# FilterBoard_Schematic.net
KiCad netlist of a schematic drawn in Altium Designer
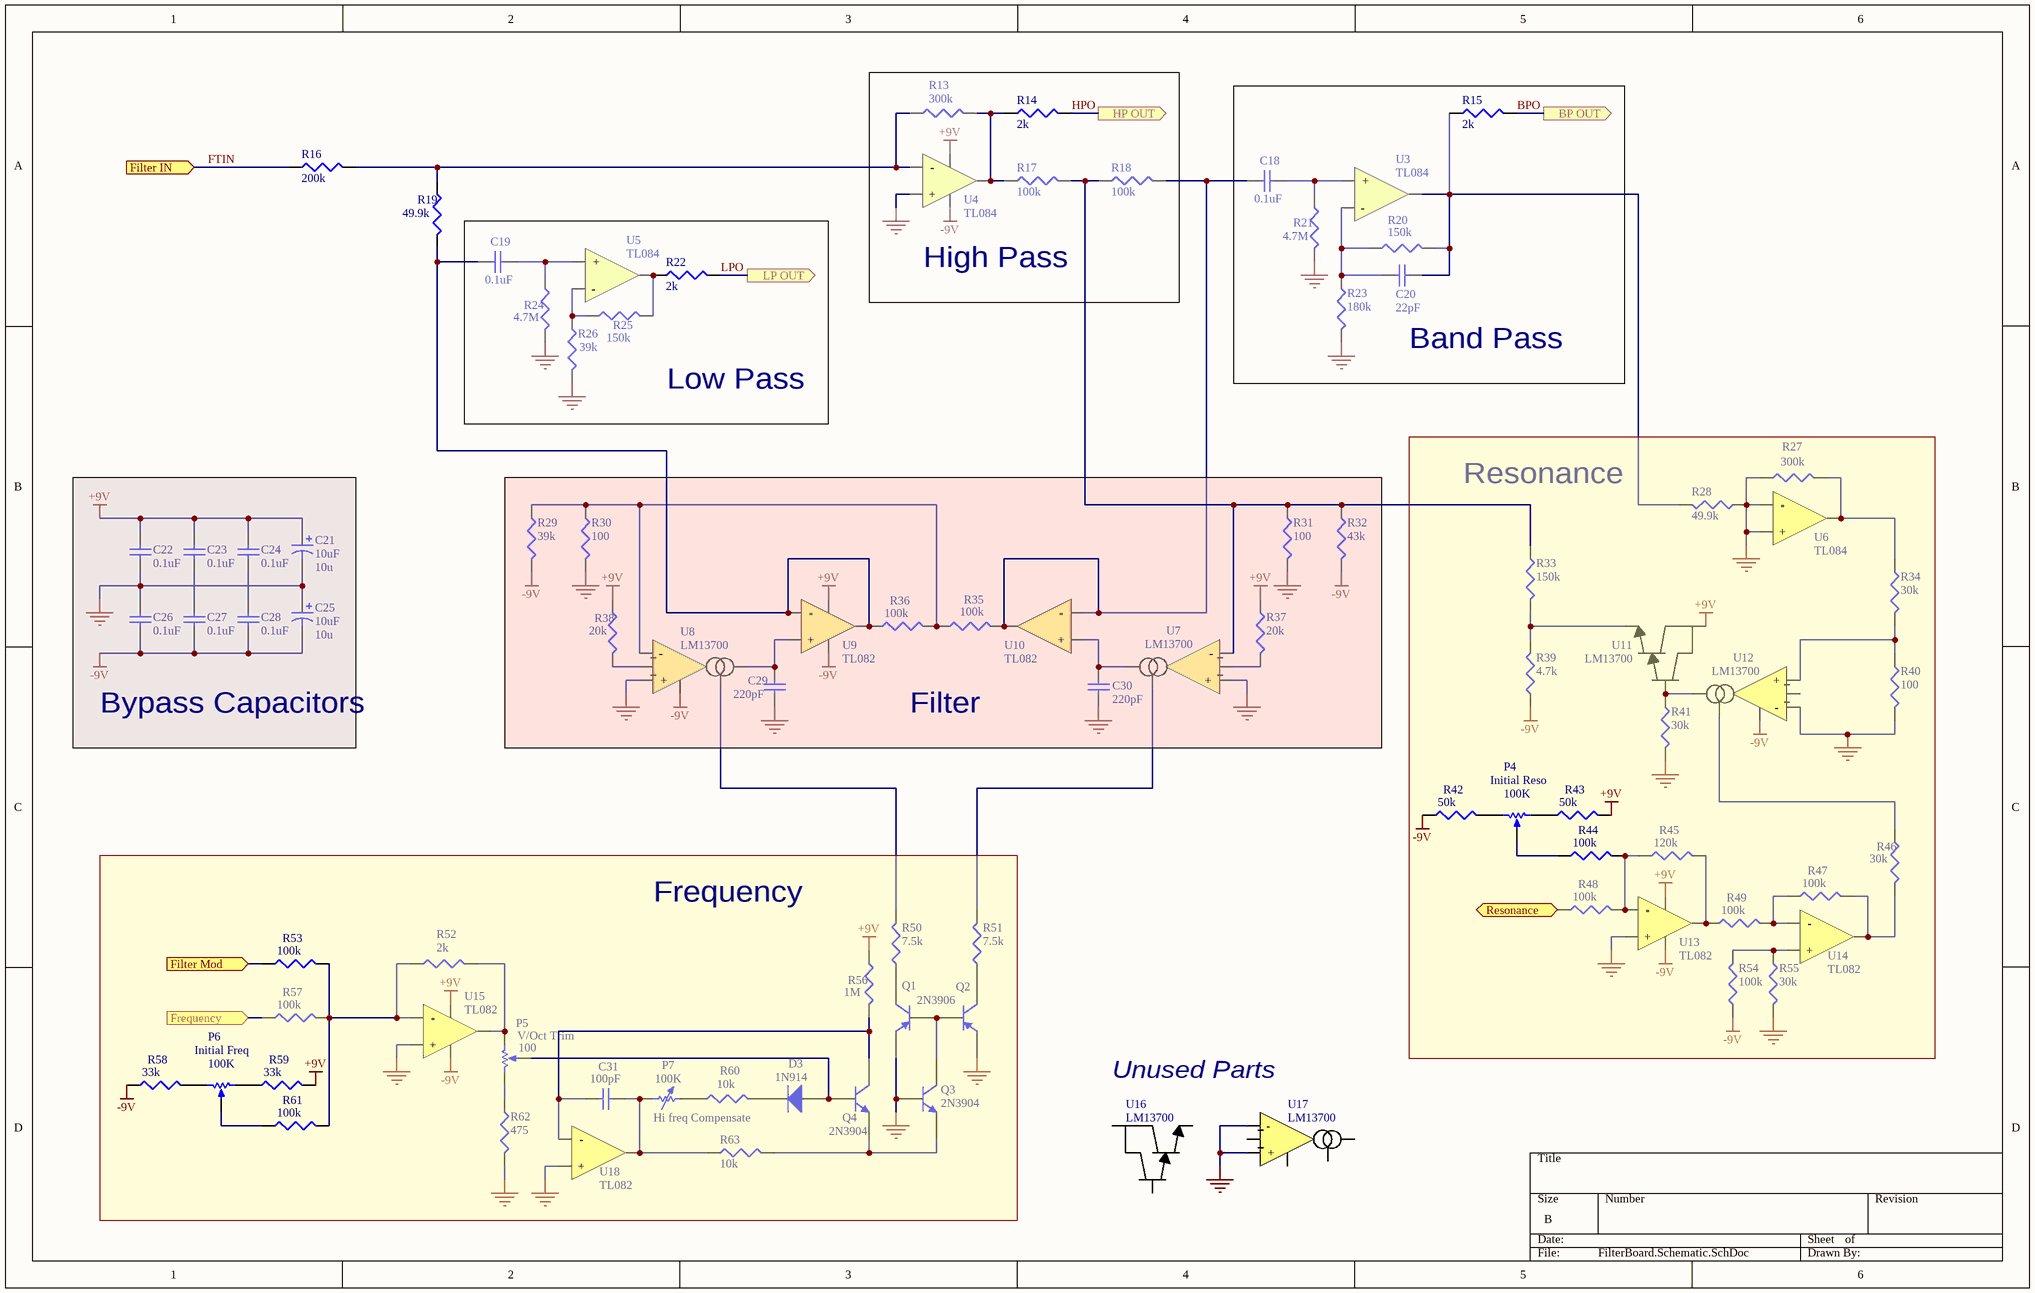
[diagram p0: FilterBoard.Schematic.SchDoc]

(export (version "E")
  (design (tool "Eeschema 10.0.6"))
  (components
    (comp (ref "C18")
      (value "0.1uF")
      (footprint "C1206")
      (description "Capacitor (Semiconductor SIM Model)")
      (fields (field (name "PUBLISHER") "Altium Limited"))
      (libsource (lib "Miscellaneous Devices") (part "Cap Semi"))
    )
    (comp (ref "C19")
      (value "0.1uF")
      (footprint "C1206")
      (description "Capacitor (Semiconductor SIM Model)")
      (fields (field (name "PUBLISHER") "Altium Limited"))
      (libsource (lib "Miscellaneous Devices") (part "Cap Semi"))
    )
    (comp (ref "C20")
      (value "22pF")
      (footprint "C1206")
      (description "Capacitor (Semiconductor SIM Model)")
      (fields (field (name "PUBLISHER") "Altium Limited"))
      (libsource (lib "Miscellaneous Devices") (part "Cap Semi"))
    )
    (comp (ref "C21")
      (value "10uF")
      (footprint "RB7.6-15")
      (description "Polarized Capacitor (Radial)")
      (fields (field (name "ALTIUM_VALUE") "10u") (field (name "PUBLISHER") "Altium Limited"))
      (libsource (lib "Miscellaneous Devices") (part "Cap Pol1"))
    )
    (comp (ref "C22")
      (value "0.1uF")
      (footprint "C1206")
      (description "Capacitor (Semiconductor SIM Model)")
      (fields (field (name "PUBLISHER") "Altium Limited"))
      (libsource (lib "Miscellaneous Devices") (part "Cap Semi"))
    )
    (comp (ref "C23")
      (value "0.1uF")
      (footprint "C1206")
      (description "Capacitor (Semiconductor SIM Model)")
      (fields (field (name "PUBLISHER") "Altium Limited"))
      (libsource (lib "Miscellaneous Devices") (part "Cap Semi"))
    )
    (comp (ref "C24")
      (value "0.1uF")
      (footprint "C1206")
      (description "Capacitor (Semiconductor SIM Model)")
      (fields (field (name "PUBLISHER") "Altium Limited"))
      (libsource (lib "Miscellaneous Devices") (part "Cap Semi"))
    )
    (comp (ref "C25")
      (value "10uF")
      (footprint "RB7.6-15")
      (description "Polarized Capacitor (Radial)")
      (fields (field (name "ALTIUM_VALUE") "10u") (field (name "PUBLISHER") "Altium Limited"))
      (libsource (lib "Miscellaneous Devices") (part "Cap Pol1"))
    )
    (comp (ref "C26")
      (value "0.1uF")
      (footprint "C1206")
      (description "Capacitor (Semiconductor SIM Model)")
      (fields (field (name "PUBLISHER") "Altium Limited"))
      (libsource (lib "Miscellaneous Devices") (part "Cap Semi"))
    )
    (comp (ref "C27")
      (value "0.1uF")
      (footprint "C1206")
      (description "Capacitor (Semiconductor SIM Model)")
      (fields (field (name "PUBLISHER") "Altium Limited"))
      (libsource (lib "Miscellaneous Devices") (part "Cap Semi"))
    )
    (comp (ref "C28")
      (value "0.1uF")
      (footprint "C1206")
      (description "Capacitor (Semiconductor SIM Model)")
      (fields (field (name "PUBLISHER") "Altium Limited"))
      (libsource (lib "Miscellaneous Devices") (part "Cap Semi"))
    )
    (comp (ref "C29")
      (value "220pF")
      (footprint "C1206")
      (description "Capacitor (Semiconductor SIM Model)")
      (fields (field (name "PUBLISHER") "Altium Limited"))
      (libsource (lib "Miscellaneous Devices") (part "Cap Semi"))
    )
    (comp (ref "C30")
      (value "220pF")
      (footprint "C1206")
      (description "Capacitor (Semiconductor SIM Model)")
      (fields (field (name "PUBLISHER") "Altium Limited"))
      (libsource (lib "Miscellaneous Devices") (part "Cap Semi"))
    )
    (comp (ref "C31")
      (value "100pF")
      (footprint "C1206")
      (description "Capacitor (Semiconductor SIM Model)")
      (fields (field (name "PUBLISHER") "Altium Limited"))
      (libsource (lib "Miscellaneous Devices") (part "Cap Semi"))
    )
    (comp (ref "D3")
      (value "1N914")
      (footprint "DO-41")
      (description "1 Amp General Purpose Rectifier")
      (fields (field (name "PUBLISHER") "Altium Limited"))
      (libsource (lib "Miscellaneous Devices") (part "Diode 1N4001"))
    )
    (comp (ref "P4")
      (value "Initial Reso")
      (footprint "VR5")
      (description "Potentiometer")
      (fields (field (name "ALTIUM_VALUE") "100K") (field (name "PUBLISHER") "Altium Limited"))
      (libsource (lib "Miscellaneous Devices") (part "RPot"))
    )
    (comp (ref "P5")
      (value "V/Oct Trim")
      (footprint "VR5")
      (description "Potentiometer")
      (fields (field (name "ALTIUM_VALUE") "100") (field (name "PUBLISHER") "Altium Limited"))
      (libsource (lib "Miscellaneous Devices") (part "RPot"))
    )
    (comp (ref "P6")
      (value "Initial Freq")
      (footprint "VR5")
      (description "Potentiometer")
      (fields (field (name "ALTIUM_VALUE") "100K") (field (name "PUBLISHER") "Altium Limited"))
      (libsource (lib "Miscellaneous Devices") (part "RPot"))
    )
    (comp (ref "P7")
      (value "Hi freq Compensate")
      (footprint "AXIAL-0.7")
      (description "Variable Resistor")
      (fields (field (name "ALTIUM_VALUE") "100K") (field (name "PUBLISHER") "Altium Limited"))
      (libsource (lib "Miscellaneous Devices") (part "Res Adj1"))
    )
    (comp (ref "Q1")
      (value "2N3906")
      (footprint "TO-92A")
      (description "PNP General Purpose Amplifier")
      (fields (field (name "PUBLISHER") "Altium Limited"))
      (libsource (lib "Miscellaneous Devices") (part "2N3906"))
    )
    (comp (ref "Q2")
      (value "2N3906")
      (footprint "TO-92A")
      (description "PNP General Purpose Amplifier")
      (fields (field (name "PUBLISHER") "Altium Limited"))
      (libsource (lib "Miscellaneous Devices") (part "2N3906"))
    )
    (comp (ref "Q3")
      (value "2N3904")
      (footprint "TO-92A")
      (description "NPN General Purpose Amplifier")
      (fields (field (name "PUBLISHER") "Altium Limited"))
      (libsource (lib "Miscellaneous Devices") (part "2N3904"))
    )
    (comp (ref "Q4")
      (value "2N3904")
      (footprint "TO-92A")
      (description "NPN General Purpose Amplifier")
      (fields (field (name "PUBLISHER") "Altium Limited"))
      (libsource (lib "Miscellaneous Devices") (part "2N3904"))
    )
    (comp (ref "R13")
      (value "300k")
      (footprint "J1-0603")
      (description "Resistor")
      (fields (field (name "PUBLISHER") "Altium Limited"))
      (libsource (lib "Miscellaneous Devices") (part "Res3"))
    )
    (comp (ref "R14")
      (value "2k")
      (footprint "J1-0603")
      (description "Resistor")
      (fields (field (name "PUBLISHER") "Altium Limited"))
      (libsource (lib "Miscellaneous Devices") (part "Res3"))
    )
    (comp (ref "R15")
      (value "2k")
      (footprint "J1-0603")
      (description "Resistor")
      (fields (field (name "PUBLISHER") "Altium Limited"))
      (libsource (lib "Miscellaneous Devices") (part "Res3"))
    )
    (comp (ref "R16")
      (value "200k")
      (footprint "J1-0603")
      (description "Resistor")
      (fields (field (name "PUBLISHER") "Altium Limited"))
      (libsource (lib "Miscellaneous Devices") (part "Res3"))
    )
    (comp (ref "R17")
      (value "100k")
      (footprint "J1-0603")
      (description "Resistor")
      (fields (field (name "PUBLISHER") "Altium Limited"))
      (libsource (lib "Miscellaneous Devices") (part "Res3"))
    )
    (comp (ref "R18")
      (value "100k")
      (footprint "J1-0603")
      (description "Resistor")
      (fields (field (name "PUBLISHER") "Altium Limited"))
      (libsource (lib "Miscellaneous Devices") (part "Res3"))
    )
    (comp (ref "R19")
      (value "49.9k")
      (footprint "J1-0603")
      (description "Resistor")
      (fields (field (name "PUBLISHER") "Altium Limited"))
      (libsource (lib "Miscellaneous Devices") (part "Res3"))
    )
    (comp (ref "R20")
      (value "150k")
      (footprint "J1-0603")
      (description "Resistor")
      (fields (field (name "PUBLISHER") "Altium Limited"))
      (libsource (lib "Miscellaneous Devices") (part "Res3"))
    )
    (comp (ref "R21")
      (value "4.7M")
      (footprint "J1-0603")
      (description "Resistor")
      (fields (field (name "PUBLISHER") "Altium Limited"))
      (libsource (lib "Miscellaneous Devices") (part "Res3"))
    )
    (comp (ref "R22")
      (value "2k")
      (footprint "J1-0603")
      (description "Resistor")
      (fields (field (name "PUBLISHER") "Altium Limited"))
      (libsource (lib "Miscellaneous Devices") (part "Res3"))
    )
    (comp (ref "R23")
      (value "180k")
      (footprint "J1-0603")
      (description "Resistor")
      (fields (field (name "PUBLISHER") "Altium Limited"))
      (libsource (lib "Miscellaneous Devices") (part "Res3"))
    )
    (comp (ref "R24")
      (value "4.7M")
      (footprint "J1-0603")
      (description "Resistor")
      (fields (field (name "PUBLISHER") "Altium Limited"))
      (libsource (lib "Miscellaneous Devices") (part "Res3"))
    )
    (comp (ref "R25")
      (value "150k")
      (footprint "J1-0603")
      (description "Resistor")
      (fields (field (name "PUBLISHER") "Altium Limited"))
      (libsource (lib "Miscellaneous Devices") (part "Res3"))
    )
    (comp (ref "R26")
      (value "39k")
      (footprint "J1-0603")
      (description "Resistor")
      (fields (field (name "PUBLISHER") "Altium Limited"))
      (libsource (lib "Miscellaneous Devices") (part "Res3"))
    )
    (comp (ref "R27")
      (value "300k")
      (footprint "J1-0603")
      (description "Resistor")
      (fields (field (name "PUBLISHER") "Altium Limited"))
      (libsource (lib "Miscellaneous Devices") (part "Res3"))
    )
    (comp (ref "R28")
      (value "49.9k")
      (footprint "J1-0603")
      (description "Resistor")
      (fields (field (name "PUBLISHER") "Altium Limited"))
      (libsource (lib "Miscellaneous Devices") (part "Res3"))
    )
    (comp (ref "R29")
      (value "39k")
      (footprint "J1-0603")
      (description "Resistor")
      (fields (field (name "PUBLISHER") "Altium Limited"))
      (libsource (lib "Miscellaneous Devices") (part "Res3"))
    )
    (comp (ref "R30")
      (value "100")
      (footprint "J1-0603")
      (description "Resistor")
      (fields (field (name "PUBLISHER") "Altium Limited"))
      (libsource (lib "Miscellaneous Devices") (part "Res3"))
    )
    (comp (ref "R31")
      (value "100")
      (footprint "J1-0603")
      (description "Resistor")
      (fields (field (name "PUBLISHER") "Altium Limited"))
      (libsource (lib "Miscellaneous Devices") (part "Res3"))
    )
    (comp (ref "R32")
      (value "43k")
      (footprint "J1-0603")
      (description "Resistor")
      (fields (field (name "PUBLISHER") "Altium Limited"))
      (libsource (lib "Miscellaneous Devices") (part "Res3"))
    )
    (comp (ref "R33")
      (value "150k")
      (footprint "J1-0603")
      (description "Resistor")
      (fields (field (name "PUBLISHER") "Altium Limited"))
      (libsource (lib "Miscellaneous Devices") (part "Res3"))
    )
    (comp (ref "R34")
      (value "30k")
      (footprint "J1-0603")
      (description "Resistor")
      (fields (field (name "PUBLISHER") "Altium Limited"))
      (libsource (lib "Miscellaneous Devices") (part "Res3"))
    )
    (comp (ref "R35")
      (value "100k")
      (footprint "J1-0603")
      (description "Resistor")
      (fields (field (name "PUBLISHER") "Altium Limited"))
      (libsource (lib "Miscellaneous Devices") (part "Res3"))
    )
    (comp (ref "R36")
      (value "100k")
      (footprint "J1-0603")
      (description "Resistor")
      (fields (field (name "PUBLISHER") "Altium Limited"))
      (libsource (lib "Miscellaneous Devices") (part "Res3"))
    )
    (comp (ref "R37")
      (value "20k")
      (footprint "J1-0603")
      (description "Resistor")
      (fields (field (name "PUBLISHER") "Altium Limited"))
      (libsource (lib "Miscellaneous Devices") (part "Res3"))
    )
    (comp (ref "R38")
      (value "20k")
      (footprint "J1-0603")
      (description "Resistor")
      (fields (field (name "PUBLISHER") "Altium Limited"))
      (libsource (lib "Miscellaneous Devices") (part "Res3"))
    )
    (comp (ref "R39")
      (value "4.7k")
      (footprint "J1-0603")
      (description "Resistor")
      (fields (field (name "PUBLISHER") "Altium Limited"))
      (libsource (lib "Miscellaneous Devices") (part "Res3"))
    )
    (comp (ref "R40")
      (value "100")
      (footprint "J1-0603")
      (description "Resistor")
      (fields (field (name "PUBLISHER") "Altium Limited"))
      (libsource (lib "Miscellaneous Devices") (part "Res3"))
    )
    (comp (ref "R41")
      (value "30k")
      (footprint "J1-0603")
      (description "Resistor")
      (fields (field (name "PUBLISHER") "Altium Limited"))
      (libsource (lib "Miscellaneous Devices") (part "Res3"))
    )
    (comp (ref "R42")
      (value "50k")
      (footprint "J1-0603")
      (description "Resistor")
      (fields (field (name "PUBLISHER") "Altium Limited"))
      (libsource (lib "Miscellaneous Devices") (part "Res3"))
    )
    (comp (ref "R43")
      (value "50k")
      (footprint "J1-0603")
      (description "Resistor")
      (fields (field (name "PUBLISHER") "Altium Limited"))
      (libsource (lib "Miscellaneous Devices") (part "Res3"))
    )
    (comp (ref "R44")
      (value "100k")
      (footprint "J1-0603")
      (description "Resistor")
      (fields (field (name "PUBLISHER") "Altium Limited"))
      (libsource (lib "Miscellaneous Devices") (part "Res3"))
    )
    (comp (ref "R45")
      (value "120k")
      (footprint "J1-0603")
      (description "Resistor")
      (fields (field (name "PUBLISHER") "Altium Limited"))
      (libsource (lib "Miscellaneous Devices") (part "Res3"))
    )
    (comp (ref "R46")
      (value "30k")
      (footprint "J1-0603")
      (description "Resistor")
      (fields (field (name "PUBLISHER") "Altium Limited"))
      (libsource (lib "Miscellaneous Devices") (part "Res3"))
    )
    (comp (ref "R47")
      (value "100k")
      (footprint "J1-0603")
      (description "Resistor")
      (fields (field (name "PUBLISHER") "Altium Limited"))
      (libsource (lib "Miscellaneous Devices") (part "Res3"))
    )
    (comp (ref "R48")
      (value "100k")
      (footprint "J1-0603")
      (description "Resistor")
      (fields (field (name "PUBLISHER") "Altium Limited"))
      (libsource (lib "Miscellaneous Devices") (part "Res3"))
    )
    (comp (ref "R49")
      (value "100k")
      (footprint "J1-0603")
      (description "Resistor")
      (fields (field (name "PUBLISHER") "Altium Limited"))
      (libsource (lib "Miscellaneous Devices") (part "Res3"))
    )
    (comp (ref "R50")
      (value "7.5k")
      (footprint "J1-0603")
      (description "Resistor")
      (fields (field (name "PUBLISHER") "Altium Limited"))
      (libsource (lib "Miscellaneous Devices") (part "Res3"))
    )
    (comp (ref "R51")
      (value "7.5k")
      (footprint "J1-0603")
      (description "Resistor")
      (fields (field (name "PUBLISHER") "Altium Limited"))
      (libsource (lib "Miscellaneous Devices") (part "Res3"))
    )
    (comp (ref "R52")
      (value "2k")
      (footprint "J1-0603")
      (description "Resistor")
      (fields (field (name "PUBLISHER") "Altium Limited"))
      (libsource (lib "Miscellaneous Devices") (part "Res3"))
    )
    (comp (ref "R53")
      (value "100k")
      (footprint "J1-0603")
      (description "Resistor")
      (fields (field (name "PUBLISHER") "Altium Limited"))
      (libsource (lib "Miscellaneous Devices") (part "Res3"))
    )
    (comp (ref "R54")
      (value "100k")
      (footprint "J1-0603")
      (description "Resistor")
      (fields (field (name "PUBLISHER") "Altium Limited"))
      (libsource (lib "Miscellaneous Devices") (part "Res3"))
    )
    (comp (ref "R55")
      (value "30k")
      (footprint "J1-0603")
      (description "Resistor")
      (fields (field (name "PUBLISHER") "Altium Limited"))
      (libsource (lib "Miscellaneous Devices") (part "Res3"))
    )
    (comp (ref "R56")
      (value "1M")
      (footprint "J1-0603")
      (description "Resistor")
      (fields (field (name "PUBLISHER") "Altium Limited"))
      (libsource (lib "Miscellaneous Devices") (part "Res3"))
    )
    (comp (ref "R57")
      (value "100k")
      (footprint "J1-0603")
      (description "Resistor")
      (fields (field (name "PUBLISHER") "Altium Limited"))
      (libsource (lib "Miscellaneous Devices") (part "Res3"))
    )
    (comp (ref "R58")
      (value "33k")
      (footprint "J1-0603")
      (description "Resistor")
      (fields (field (name "PUBLISHER") "Altium Limited"))
      (libsource (lib "Miscellaneous Devices") (part "Res3"))
    )
    (comp (ref "R59")
      (value "33k")
      (footprint "J1-0603")
      (description "Resistor")
      (fields (field (name "PUBLISHER") "Altium Limited"))
      (libsource (lib "Miscellaneous Devices") (part "Res3"))
    )
    (comp (ref "R60")
      (value "10k")
      (footprint "J1-0603")
      (description "Resistor")
      (fields (field (name "PUBLISHER") "Altium Limited"))
      (libsource (lib "Miscellaneous Devices") (part "Res3"))
    )
    (comp (ref "R61")
      (value "100k")
      (footprint "J1-0603")
      (description "Resistor")
      (fields (field (name "PUBLISHER") "Altium Limited"))
      (libsource (lib "Miscellaneous Devices") (part "Res3"))
    )
    (comp (ref "R62")
      (value "475")
      (footprint "J1-0603")
      (description "Resistor")
      (fields (field (name "PUBLISHER") "Altium Limited"))
      (libsource (lib "Miscellaneous Devices") (part "Res3"))
    )
    (comp (ref "R63")
      (value "10k")
      (footprint "J1-0603")
      (description "Resistor")
      (fields (field (name "PUBLISHER") "Altium Limited"))
      (libsource (lib "Miscellaneous Devices") (part "Res3"))
    )
    (comp (ref "U3") (value "TL084") (libsource (lib "") (part "TL084_1")))
    (comp (ref "U4") (value "TL084") (libsource (lib "") (part "TL084_2")))
    (comp (ref "U5") (value "TL084") (libsource (lib "") (part "TL084_1")))
    (comp (ref "U6") (value "TL084") (libsource (lib "SynthyTwo.Components") (part "TL084")))
    (comp (ref "U7") (value "LM13700") (libsource (lib "SynthyTwo.Components") (part "LM13700")))
    (comp (ref "U8") (value "LM13700") (libsource (lib "SynthyTwo.Components") (part "LM13700")))
    (comp (ref "U9") (value "TL082") (libsource (lib "") (part "TL082_1")))
    (comp (ref "U10") (value "TL082") (libsource (lib "SynthyTwo.Components") (part "TL082")))
    (comp (ref "U11") (value "LM13700") (libsource (lib "SynthyTwo.Components") (part "LM13700_1")))
    (comp (ref "U12") (value "LM13700") (libsource (lib "SynthyTwo.Components") (part "LM13700")))
    (comp (ref "U13") (value "TL082") (libsource (lib "") (part "TL082_1")))
    (comp (ref "U14") (value "TL082") (libsource (lib "SynthyTwo.Components") (part "TL082")))
    (comp (ref "U15") (value "TL082") (libsource (lib "") (part "TL082_1")))
    (comp (ref "U16") (value "LM13700") (libsource (lib "SynthyTwo.Components") (part "LM13700_1")))
    (comp (ref "U17") (value "LM13700") (libsource (lib "SynthyTwo.Components") (part "LM13700")))
    (comp (ref "U18") (value "TL082") (libsource (lib "SynthyTwo.Components") (part "TL082")))
  )
  (nets
    (net (code "1") (name "+9V") (class "Default")
      (node (ref "C21") (pin "1") (pinfunction "1_1") (pintype "passive"))
      (node (ref "C22") (pin "2") (pinfunction "2_2") (pintype "passive"))
      (node (ref "C23") (pin "2") (pinfunction "2_2") (pintype "passive"))
      (node (ref "C24") (pin "2") (pinfunction "2_2") (pintype "passive"))
      (node (ref "R37") (pin "1") (pinfunction "1_1") (pintype "passive"))
      (node (ref "R38") (pin "1") (pinfunction "1_1") (pintype "passive"))
      (node (ref "R43") (pin "2") (pinfunction "2_2") (pintype "passive"))
      (node (ref "R56") (pin "1") (pinfunction "1_1") (pintype "passive"))
      (node (ref "R59") (pin "2") (pinfunction "2_2") (pintype "passive"))
      (node (ref "U11") (pin "11") (pinfunction "V+_11") (pintype "passive"))
      (node (ref "U13") (pin "8") (pinfunction "VCC+_8") (pintype "passive"))
      (node (ref "U15") (pin "8") (pinfunction "VCC+_8") (pintype "passive"))
      (node (ref "U4") (pin "4") (pinfunction "VCC+_4") (pintype "passive"))
      (node (ref "U9") (pin "8") (pinfunction "VCC+_8") (pintype "passive"))
    )
    (net (code "2") (name "-9V") (class "Default")
      (node (ref "C25") (pin "2") (pinfunction "2_2") (pintype "passive"))
      (node (ref "C26") (pin "1") (pinfunction "1_1") (pintype "passive"))
      (node (ref "C27") (pin "1") (pinfunction "1_1") (pintype "passive"))
      (node (ref "C28") (pin "1") (pinfunction "1_1") (pintype "passive"))
      (node (ref "R29") (pin "2") (pinfunction "2_2") (pintype "passive"))
      (node (ref "R32") (pin "2") (pinfunction "2_2") (pintype "passive"))
      (node (ref "R39") (pin "1") (pinfunction "1_1") (pintype "passive"))
      (node (ref "R42") (pin "1") (pinfunction "1_1") (pintype "passive"))
      (node (ref "R54") (pin "1") (pinfunction "1_1") (pintype "passive"))
      (node (ref "R58") (pin "1") (pinfunction "1_1") (pintype "passive"))
      (node (ref "U12") (pin "6") (pinfunction "VCC-_6") (pintype "passive"))
      (node (ref "U13") (pin "4") (pinfunction "VCC-_4") (pintype "passive"))
      (node (ref "U15") (pin "4") (pinfunction "VCC-_4") (pintype "passive"))
      (node (ref "U4") (pin "11") (pinfunction "VCC-_11") (pintype "passive"))
      (node (ref "U8") (pin "6") (pinfunction "VCC-_6") (pintype "passive"))
      (node (ref "U9") (pin "4") (pinfunction "VCC-_4") (pintype "passive"))
    )
    (net (code "3") (name "/BPO") (class "Default")
      (node (ref "R15") (pin "2") (pinfunction "2_2") (pintype "passive"))
    )
    (net (code "4") (name "/FTIN") (class "Default")
      (node (ref "R16") (pin "1") (pinfunction "1_1") (pintype "passive"))
    )
    (net (code "5") (name "/Filter Mod") (class "Default")
      (node (ref "R53") (pin "1") (pinfunction "1_1") (pintype "passive"))
    )
    (net (code "6") (name "/Frequency") (class "Default")
      (node (ref "R57") (pin "1") (pinfunction "1_1") (pintype "passive"))
    )
    (net (code "7") (name "/HPO") (class "Default")
      (node (ref "R14") (pin "2") (pinfunction "2_2") (pintype "passive"))
    )
    (net (code "8") (name "/LPO") (class "Default")
      (node (ref "R22") (pin "2") (pinfunction "2_2") (pintype "passive"))
    )
    (net (code "9") (name "/Resonance") (class "Default")
      (node (ref "R48") (pin "1") (pinfunction "1_1") (pintype "passive"))
    )
    (net (code "10") (name "GND") (class "Default")
      (node (ref "C21") (pin "2") (pinfunction "2_2") (pintype "passive"))
      (node (ref "C22") (pin "1") (pinfunction "1_1") (pintype "passive"))
      (node (ref "C25") (pin "1") (pinfunction "1_1") (pintype "passive"))
      (node (ref "C26") (pin "2") (pinfunction "2_2") (pintype "passive"))
      (node (ref "C29") (pin "1") (pinfunction "1_1") (pintype "passive"))
      (node (ref "C30") (pin "1") (pinfunction "1_1") (pintype "passive"))
      (node (ref "Q1") (pin "1") (pinfunction "E_1") (pintype "passive"))
      (node (ref "Q2") (pin "1") (pinfunction "E_1") (pintype "passive"))
      (node (ref "Q3") (pin "2") (pinfunction "B_2") (pintype "passive"))
      (node (ref "R21") (pin "2") (pinfunction "2_2") (pintype "passive"))
      (node (ref "R23") (pin "2") (pinfunction "2_2") (pintype "passive"))
      (node (ref "R24") (pin "2") (pinfunction "2_2") (pintype "passive"))
      (node (ref "R26") (pin "2") (pinfunction "2_2") (pintype "passive"))
      (node (ref "R27") (pin "1") (pinfunction "1_1") (pintype "passive"))
      (node (ref "R28") (pin "1") (pinfunction "1_1") (pintype "passive"))
      (node (ref "R30") (pin "2") (pinfunction "2_2") (pintype "passive"))
      (node (ref "R31") (pin "2") (pinfunction "2_2") (pintype "passive"))
      (node (ref "R40") (pin "2") (pinfunction "2_2") (pintype "passive"))
      (node (ref "R41") (pin "2") (pinfunction "2_2") (pintype "passive"))
      (node (ref "R55") (pin "2") (pinfunction "2_2") (pintype "passive"))
      (node (ref "R62") (pin "2") (pinfunction "2_2") (pintype "passive"))
      (node (ref "U12") (pin "3") (pinfunction "+_3") (pintype "passive"))
      (node (ref "U13") (pin "3") (pinfunction "+_3") (pintype "passive"))
      (node (ref "U15") (pin "3") (pinfunction "+_3") (pintype "passive"))
      (node (ref "U17") (pin "3") (pinfunction "+_3") (pintype "passive"))
      (node (ref "U17") (pin "4") (pinfunction "-_4") (pintype "passive"))
      (node (ref "U18") (pin "5") (pinfunction "+_5") (pintype "passive"))
      (node (ref "U4") (pin "3") (pinfunction "+_3") (pintype "passive"))
      (node (ref "U6") (pin "12") (pinfunction "-_12") (pintype "passive"))
      (node (ref "U6") (pin "13") (pinfunction "+_13") (pintype "passive"))
      (node (ref "U7") (pin "3") (pinfunction "+_3") (pintype "passive"))
      (node (ref "U8") (pin "3") (pinfunction "+_3") (pintype "passive"))
    )
    (net (code "11") (name "Net-(C23-Pad1)") (class "Default")
      (node (ref "C23") (pin "1") (pinfunction "1_1") (pintype "passive"))
      (node (ref "C27") (pin "2") (pinfunction "2_2") (pintype "passive"))
    )
    (net (code "12") (name "Net-(C24-Pad1)") (class "Default")
      (node (ref "C24") (pin "1") (pinfunction "1_1") (pintype "passive"))
      (node (ref "C28") (pin "2") (pinfunction "2_2") (pintype "passive"))
    )
    (net (code "13") (name "Net-(D3-A)") (class "Default")
      (node (ref "D3") (pin "1") (pinfunction "A_1") (pintype "passive"))
      (node (ref "P5") (pin "3") (pinfunction "TAP_3") (pintype "passive"))
      (node (ref "Q4") (pin "2") (pinfunction "B_2") (pintype "passive"))
    )
    (net (code "14") (name "Net-(D3-K)") (class "Default")
      (node (ref "D3") (pin "2") (pinfunction "K_2") (pintype "passive"))
      (node (ref "R60") (pin "2") (pinfunction "2_2") (pintype "passive"))
    )
    (net (code "15") (name "Net-(P4-BOT)") (class "Default")
      (node (ref "P4") (pin "2") (pinfunction "BOT_2") (pintype "passive"))
      (node (ref "R42") (pin "2") (pinfunction "2_2") (pintype "passive"))
    )
    (net (code "16") (name "Net-(P4-TAP)") (class "Default")
      (node (ref "P4") (pin "3") (pinfunction "TAP_3") (pintype "passive"))
      (node (ref "R44") (pin "1") (pinfunction "1_1") (pintype "passive"))
    )
    (net (code "17") (name "Net-(P4-TOP)") (class "Default")
      (node (ref "P4") (pin "1") (pinfunction "TOP_1") (pintype "passive"))
      (node (ref "R43") (pin "1") (pinfunction "1_1") (pintype "passive"))
    )
    (net (code "18") (name "Net-(P5-BOT)") (class "Default")
      (node (ref "P5") (pin "2") (pinfunction "BOT_2") (pintype "passive"))
      (node (ref "R62") (pin "1") (pinfunction "1_1") (pintype "passive"))
    )
    (net (code "19") (name "Net-(P5-TOP)") (class "Default")
      (node (ref "P5") (pin "1") (pinfunction "TOP_1") (pintype "passive"))
      (node (ref "R52") (pin "2") (pinfunction "2_2") (pintype "passive"))
      (node (ref "U15") (pin "1") (pinfunction "OUT_1") (pintype "passive"))
    )
    (net (code "20") (name "Net-(P6-BOT)") (class "Default")
      (node (ref "P6") (pin "2") (pinfunction "BOT_2") (pintype "passive"))
      (node (ref "R58") (pin "2") (pinfunction "2_2") (pintype "passive"))
    )
    (net (code "21") (name "Net-(P6-TAP)") (class "Default")
      (node (ref "P6") (pin "3") (pinfunction "TAP_3") (pintype "passive"))
      (node (ref "R61") (pin "1") (pinfunction "1_1") (pintype "passive"))
    )
    (net (code "22") (name "Net-(P6-TOP)") (class "Default")
      (node (ref "P6") (pin "1") (pinfunction "TOP_1") (pintype "passive"))
      (node (ref "R59") (pin "1") (pinfunction "1_1") (pintype "passive"))
    )
    (net (code "23") (name "Net-(P7-Pad2)") (class "Default")
      (node (ref "P7") (pin "2") (pinfunction "2_2") (pintype "passive"))
      (node (ref "R60") (pin "1") (pinfunction "1_1") (pintype "passive"))
    )
    (net (code "24") (name "Net-(Q1-B)") (class "Default")
      (node (ref "Q1") (pin "2") (pinfunction "B_2") (pintype "passive"))
      (node (ref "Q2") (pin "2") (pinfunction "B_2") (pintype "passive"))
      (node (ref "Q3") (pin "3") (pinfunction "C_3") (pintype "passive"))
    )
    (net (code "25") (name "Net-(Q1-C)") (class "Default")
      (node (ref "Q1") (pin "3") (pinfunction "C_3") (pintype "passive"))
      (node (ref "R50") (pin "1") (pinfunction "1_1") (pintype "passive"))
    )
    (net (code "26") (name "Net-(Q2-C)") (class "Default")
      (node (ref "Q2") (pin "3") (pinfunction "C_3") (pintype "passive"))
      (node (ref "R51") (pin "1") (pinfunction "1_1") (pintype "passive"))
    )
    (net (code "27") (name "Net-(Q3-E)") (class "Default")
      (node (ref "Q3") (pin "1") (pinfunction "E_1") (pintype "passive"))
      (node (ref "Q4") (pin "1") (pinfunction "E_1") (pintype "passive"))
      (node (ref "R63") (pin "2") (pinfunction "2_2") (pintype "passive"))
    )
    (net (code "28") (name "Net-(Q4-C)") (class "Default")
      (node (ref "C31") (pin "1") (pinfunction "1_1") (pintype "passive"))
      (node (ref "Q4") (pin "3") (pinfunction "C_3") (pintype "passive"))
      (node (ref "R56") (pin "2") (pinfunction "2_2") (pintype "passive"))
      (node (ref "U18") (pin "6") (pinfunction "-_6") (pintype "passive"))
    )
    (net (code "29") (name "Net-(R37-Pad2)") (class "Default")
      (node (ref "R37") (pin "2") (pinfunction "2_2") (pintype "passive"))
      (node (ref "U7") (pin "2") (pinfunction "2_2") (pintype "passive"))
    )
    (net (code "30") (name "Net-(R38-Pad2)") (class "Default")
      (node (ref "R38") (pin "2") (pinfunction "2_2") (pintype "passive"))
      (node (ref "U8") (pin "2") (pinfunction "2_2") (pintype "passive"))
    )
    (net (code "31") (name "Net-(U3-+)") (class "Default")
      (node (ref "C18") (pin "2") (pinfunction "2_2") (pintype "passive"))
      (node (ref "R21") (pin "1") (pinfunction "1_1") (pintype "passive"))
      (node (ref "U3") (pin "5") (pinfunction "+_5") (pintype "passive"))
    )
    (net (code "32") (name "Net-(U3--)") (class "Default")
      (node (ref "C20") (pin "1") (pinfunction "1_1") (pintype "passive"))
      (node (ref "R20") (pin "1") (pinfunction "1_1") (pintype "passive"))
      (node (ref "R23") (pin "1") (pinfunction "1_1") (pintype "passive"))
      (node (ref "U3") (pin "3") (pinfunction "-_3") (pintype "passive"))
    )
    (net (code "33") (name "Net-(U3-OUT)") (class "Default")
      (node (ref "C20") (pin "2") (pinfunction "2_2") (pintype "passive"))
      (node (ref "R15") (pin "1") (pinfunction "1_1") (pintype "passive"))
      (node (ref "R20") (pin "2") (pinfunction "2_2") (pintype "passive"))
      (node (ref "R28") (pin "2") (pinfunction "2_2") (pintype "passive"))
      (node (ref "U3") (pin "7") (pinfunction "OUT_7") (pintype "passive"))
    )
    (net (code "34") (name "Net-(U4--)") (class "Default")
      (node (ref "R13") (pin "1") (pinfunction "1_1") (pintype "passive"))
      (node (ref "R16") (pin "2") (pinfunction "2_2") (pintype "passive"))
      (node (ref "R19") (pin "1") (pinfunction "1_1") (pintype "passive"))
      (node (ref "U4") (pin "2") (pinfunction "-_2") (pintype "passive"))
    )
    (net (code "35") (name "Net-(U4-OUT)") (class "Default")
      (node (ref "R13") (pin "2") (pinfunction "2_2") (pintype "passive"))
      (node (ref "R14") (pin "1") (pinfunction "1_1") (pintype "passive"))
      (node (ref "R17") (pin "1") (pinfunction "1_1") (pintype "passive"))
      (node (ref "U4") (pin "1") (pinfunction "OUT_1") (pintype "passive"))
    )
    (net (code "36") (name "Net-(U5-+)") (class "Default")
      (node (ref "C19") (pin "2") (pinfunction "2_2") (pintype "passive"))
      (node (ref "R24") (pin "1") (pinfunction "1_1") (pintype "passive"))
      (node (ref "U5") (pin "5") (pinfunction "+_5") (pintype "passive"))
    )
    (net (code "37") (name "Net-(U5--)") (class "Default")
      (node (ref "R25") (pin "1") (pinfunction "1_1") (pintype "passive"))
      (node (ref "R26") (pin "1") (pinfunction "1_1") (pintype "passive"))
      (node (ref "U5") (pin "3") (pinfunction "-_3") (pintype "passive"))
    )
    (net (code "38") (name "Net-(U5-OUT)") (class "Default")
      (node (ref "R22") (pin "1") (pinfunction "1_1") (pintype "passive"))
      (node (ref "R25") (pin "2") (pinfunction "2_2") (pintype "passive"))
      (node (ref "U5") (pin "7") (pinfunction "OUT_7") (pintype "passive"))
    )
    (net (code "39") (name "Net-(U6-OUT)") (class "Default")
      (node (ref "R27") (pin "2") (pinfunction "2_2") (pintype "passive"))
      (node (ref "R34") (pin "1") (pinfunction "1_1") (pintype "passive"))
      (node (ref "U6") (pin "14") (pinfunction "OUT_14") (pintype "passive"))
    )
    (net (code "40") (name "Net-(U7--)") (class "Default")
      (node (ref "R17") (pin "2") (pinfunction "2_2") (pintype "passive"))
      (node (ref "R18") (pin "1") (pinfunction "1_1") (pintype "passive"))
      (node (ref "R31") (pin "1") (pinfunction "1_1") (pintype "passive"))
      (node (ref "R32") (pin "1") (pinfunction "1_1") (pintype "passive"))
      (node (ref "R33") (pin "1") (pinfunction "1_1") (pintype "passive"))
      (node (ref "U7") (pin "4") (pinfunction "-_4") (pintype "passive"))
    )
    (net (code "41") (name "Net-(U7-BIAS)") (class "Default")
      (node (ref "R51") (pin "2") (pinfunction "2_2") (pintype "passive"))
      (node (ref "U7") (pin "1") (pinfunction "BIAS_1") (pintype "passive"))
    )
    (net (code "42") (name "Net-(U8--)") (class "Default")
      (node (ref "R29") (pin "1") (pinfunction "1_1") (pintype "passive"))
      (node (ref "R30") (pin "1") (pinfunction "1_1") (pintype "passive"))
      (node (ref "R35") (pin "1") (pinfunction "1_1") (pintype "passive"))
      (node (ref "R36") (pin "2") (pinfunction "2_2") (pintype "passive"))
      (node (ref "U8") (pin "4") (pinfunction "-_4") (pintype "passive"))
    )
    (net (code "43") (name "Net-(U8-BIAS)") (class "Default")
      (node (ref "R50") (pin "2") (pinfunction "2_2") (pintype "passive"))
      (node (ref "U8") (pin "1") (pinfunction "BIAS_1") (pintype "passive"))
    )
    (net (code "44") (name "Net-(U8-OUT)") (class "Default")
      (node (ref "C29") (pin "2") (pinfunction "2_2") (pintype "passive"))
      (node (ref "U8") (pin "5") (pinfunction "OUT_5") (pintype "passive"))
      (node (ref "U9") (pin "3") (pinfunction "+_3") (pintype "passive"))
    )
    (net (code "45") (name "Net-(U9--)") (class "Default")
      (node (ref "C19") (pin "1") (pinfunction "1_1") (pintype "passive"))
      (node (ref "R19") (pin "2") (pinfunction "2_2") (pintype "passive"))
      (node (ref "R36") (pin "1") (pinfunction "1_1") (pintype "passive"))
      (node (ref "U9") (pin "1") (pinfunction "OUT_1") (pintype "passive"))
      (node (ref "U9") (pin "2") (pinfunction "-_2") (pintype "passive"))
    )
    (net (code "46") (name "Net-(U10-+)") (class "Default")
      (node (ref "C30") (pin "2") (pinfunction "2_2") (pintype "passive"))
      (node (ref "U10") (pin "5") (pinfunction "+_5") (pintype "passive"))
      (node (ref "U7") (pin "5") (pinfunction "OUT_5") (pintype "passive"))
    )
    (net (code "47") (name "Net-(U10--)") (class "Default")
      (node (ref "C18") (pin "1") (pinfunction "1_1") (pintype "passive"))
      (node (ref "R18") (pin "2") (pinfunction "2_2") (pintype "passive"))
      (node (ref "R35") (pin "2") (pinfunction "2_2") (pintype "passive"))
      (node (ref "U10") (pin "6") (pinfunction "-_6") (pintype "passive"))
      (node (ref "U10") (pin "7") (pinfunction "OUT_7") (pintype "passive"))
    )
    (net (code "48") (name "Net-(U11-BIN)") (class "Default")
      (node (ref "R41") (pin "1") (pinfunction "1_1") (pintype "passive"))
      (node (ref "U11") (pin "7") (pinfunction "BIN_7") (pintype "passive"))
      (node (ref "U12") (pin "5") (pinfunction "OUT_5") (pintype "passive"))
    )
    (net (code "49") (name "Net-(U11-BOUT)") (class "Default")
      (node (ref "R33") (pin "2") (pinfunction "2_2") (pintype "passive"))
      (node (ref "R39") (pin "2") (pinfunction "2_2") (pintype "passive"))
      (node (ref "U11") (pin "8") (pinfunction "BOUT_8") (pintype "passive"))
    )
    (net (code "50") (name "Net-(U12--)") (class "Default")
      (node (ref "R34") (pin "2") (pinfunction "2_2") (pintype "passive"))
      (node (ref "R40") (pin "1") (pinfunction "1_1") (pintype "passive"))
      (node (ref "U12") (pin "4") (pinfunction "-_4") (pintype "passive"))
    )
    (net (code "51") (name "Net-(U12-BIAS)") (class "Default")
      (node (ref "R46") (pin "1") (pinfunction "1_1") (pintype "passive"))
      (node (ref "U12") (pin "1") (pinfunction "BIAS_1") (pintype "passive"))
    )
    (net (code "52") (name "Net-(U13--)") (class "Default")
      (node (ref "R44") (pin "2") (pinfunction "2_2") (pintype "passive"))
      (node (ref "R45") (pin "1") (pinfunction "1_1") (pintype "passive"))
      (node (ref "R48") (pin "2") (pinfunction "2_2") (pintype "passive"))
      (node (ref "U13") (pin "2") (pinfunction "-_2") (pintype "passive"))
    )
    (net (code "53") (name "Net-(U13-OUT)") (class "Default")
      (node (ref "R45") (pin "2") (pinfunction "2_2") (pintype "passive"))
      (node (ref "R49") (pin "1") (pinfunction "1_1") (pintype "passive"))
      (node (ref "U13") (pin "1") (pinfunction "OUT_1") (pintype "passive"))
    )
    (net (code "54") (name "Net-(U14-+)") (class "Default")
      (node (ref "R54") (pin "2") (pinfunction "2_2") (pintype "passive"))
      (node (ref "R55") (pin "1") (pinfunction "1_1") (pintype "passive"))
      (node (ref "U14") (pin "5") (pinfunction "+_5") (pintype "passive"))
    )
    (net (code "55") (name "Net-(U14--)") (class "Default")
      (node (ref "R47") (pin "1") (pinfunction "1_1") (pintype "passive"))
      (node (ref "R49") (pin "2") (pinfunction "2_2") (pintype "passive"))
      (node (ref "U14") (pin "6") (pinfunction "-_6") (pintype "passive"))
    )
    (net (code "56") (name "Net-(U14-OUT)") (class "Default")
      (node (ref "R46") (pin "2") (pinfunction "2_2") (pintype "passive"))
      (node (ref "R47") (pin "2") (pinfunction "2_2") (pintype "passive"))
      (node (ref "U14") (pin "7") (pinfunction "OUT_7") (pintype "passive"))
    )
    (net (code "57") (name "Net-(U15--)") (class "Default")
      (node (ref "R52") (pin "1") (pinfunction "1_1") (pintype "passive"))
      (node (ref "R53") (pin "2") (pinfunction "2_2") (pintype "passive"))
      (node (ref "R57") (pin "2") (pinfunction "2_2") (pintype "passive"))
      (node (ref "R61") (pin "2") (pinfunction "2_2") (pintype "passive"))
      (node (ref "U15") (pin "2") (pinfunction "-_2") (pintype "passive"))
    )
    (net (code "58") (name "Net-(U18-OUT)") (class "Default")
      (node (ref "C31") (pin "2") (pinfunction "2_2") (pintype "passive"))
      (node (ref "P7") (pin "1") (pinfunction "1_1") (pintype "passive"))
      (node (ref "R63") (pin "1") (pinfunction "1_1") (pintype "passive"))
      (node (ref "U18") (pin "7") (pinfunction "OUT_7") (pintype "passive"))
    )
    (net (code "59") (name "unconnected-(U3-VCC+-Pad6)") (class "Default")
      (node (ref "U3") (pin "6") (pinfunction "VCC+_6") (pintype "passive"))
    )
    (net (code "60") (name "unconnected-(U3-VCC--Pad11)") (class "Default")
      (node (ref "U3") (pin "11") (pinfunction "VCC-_11") (pintype "passive"))
    )
    (net (code "61") (name "unconnected-(U5-VCC+-Pad6)") (class "Default")
      (node (ref "U5") (pin "6") (pinfunction "VCC+_6") (pintype "passive"))
    )
    (net (code "62") (name "unconnected-(U5-VCC--Pad11)") (class "Default")
      (node (ref "U5") (pin "11") (pinfunction "VCC-_11") (pintype "passive"))
    )
    (net (code "63") (name "unconnected-(U6-VCC+-Pad1)") (class "Default")
      (node (ref "U6") (pin "1") (pinfunction "VCC+_1") (pintype "passive"))
    )
    (net (code "64") (name "unconnected-(U6-VCC--Pad11)") (class "Default")
      (node (ref "U6") (pin "11") (pinfunction "VCC-_11") (pintype "passive"))
    )
    (net (code "65") (name "unconnected-(U7-VCC--Pad6)") (class "Default")
      (node (ref "U7") (pin "6") (pinfunction "VCC-_6") (pintype "passive"))
    )
    (net (code "66") (name "unconnected-(U10-VCC+-Pad8)") (class "Default")
      (node (ref "U10") (pin "8") (pinfunction "VCC+_8") (pintype "passive"))
    )
    (net (code "67") (name "unconnected-(U10-VCC--Pad4)") (class "Default")
      (node (ref "U10") (pin "4") (pinfunction "VCC-_4") (pintype "passive"))
    )
    (net (code "68") (name "unconnected-(U12-Pad2)") (class "Default")
      (node (ref "U12") (pin "2") (pinfunction "2_2") (pintype "passive"))
    )
    (net (code "69") (name "unconnected-(U14-VCC+-Pad8)") (class "Default")
      (node (ref "U14") (pin "8") (pinfunction "VCC+_8") (pintype "passive"))
    )
    (net (code "70") (name "unconnected-(U14-VCC--Pad4)") (class "Default")
      (node (ref "U14") (pin "4") (pinfunction "VCC-_4") (pintype "passive"))
    )
    (net (code "71") (name "unconnected-(U16-BIN-Pad7)") (class "Default")
      (node (ref "U16") (pin "7") (pinfunction "BIN_7") (pintype "passive"))
    )
    (net (code "72") (name "unconnected-(U16-BOUT-Pad8)") (class "Default")
      (node (ref "U16") (pin "8") (pinfunction "BOUT_8") (pintype "passive"))
    )
    (net (code "73") (name "unconnected-(U16-V+-Pad11)") (class "Default")
      (node (ref "U16") (pin "11") (pinfunction "V+_11") (pintype "passive"))
    )
    (net (code "74") (name "unconnected-(U17-BIAS-Pad1)") (class "Default")
      (node (ref "U17") (pin "1") (pinfunction "BIAS_1") (pintype "passive"))
    )
    (net (code "75") (name "unconnected-(U17-OUT-Pad5)") (class "Default")
      (node (ref "U17") (pin "5") (pinfunction "OUT_5") (pintype "passive"))
    )
    (net (code "76") (name "unconnected-(U17-Pad2)") (class "Default")
      (node (ref "U17") (pin "2") (pinfunction "2_2") (pintype "passive"))
    )
    (net (code "77") (name "unconnected-(U17-VCC--Pad6)") (class "Default")
      (node (ref "U17") (pin "6") (pinfunction "VCC-_6") (pintype "passive"))
    )
    (net (code "78") (name "unconnected-(U18-VCC+-Pad8)") (class "Default")
      (node (ref "U18") (pin "8") (pinfunction "VCC+_8") (pintype "passive"))
    )
    (net (code "79") (name "unconnected-(U18-VCC--Pad4)") (class "Default")
      (node (ref "U18") (pin "4") (pinfunction "VCC-_4") (pintype "passive"))
    )
  )
)
